# SCH_CapibaraZero_Navigation_Board_2024-0.net
KiCad netlist of a schematic drawn in EasyEDA
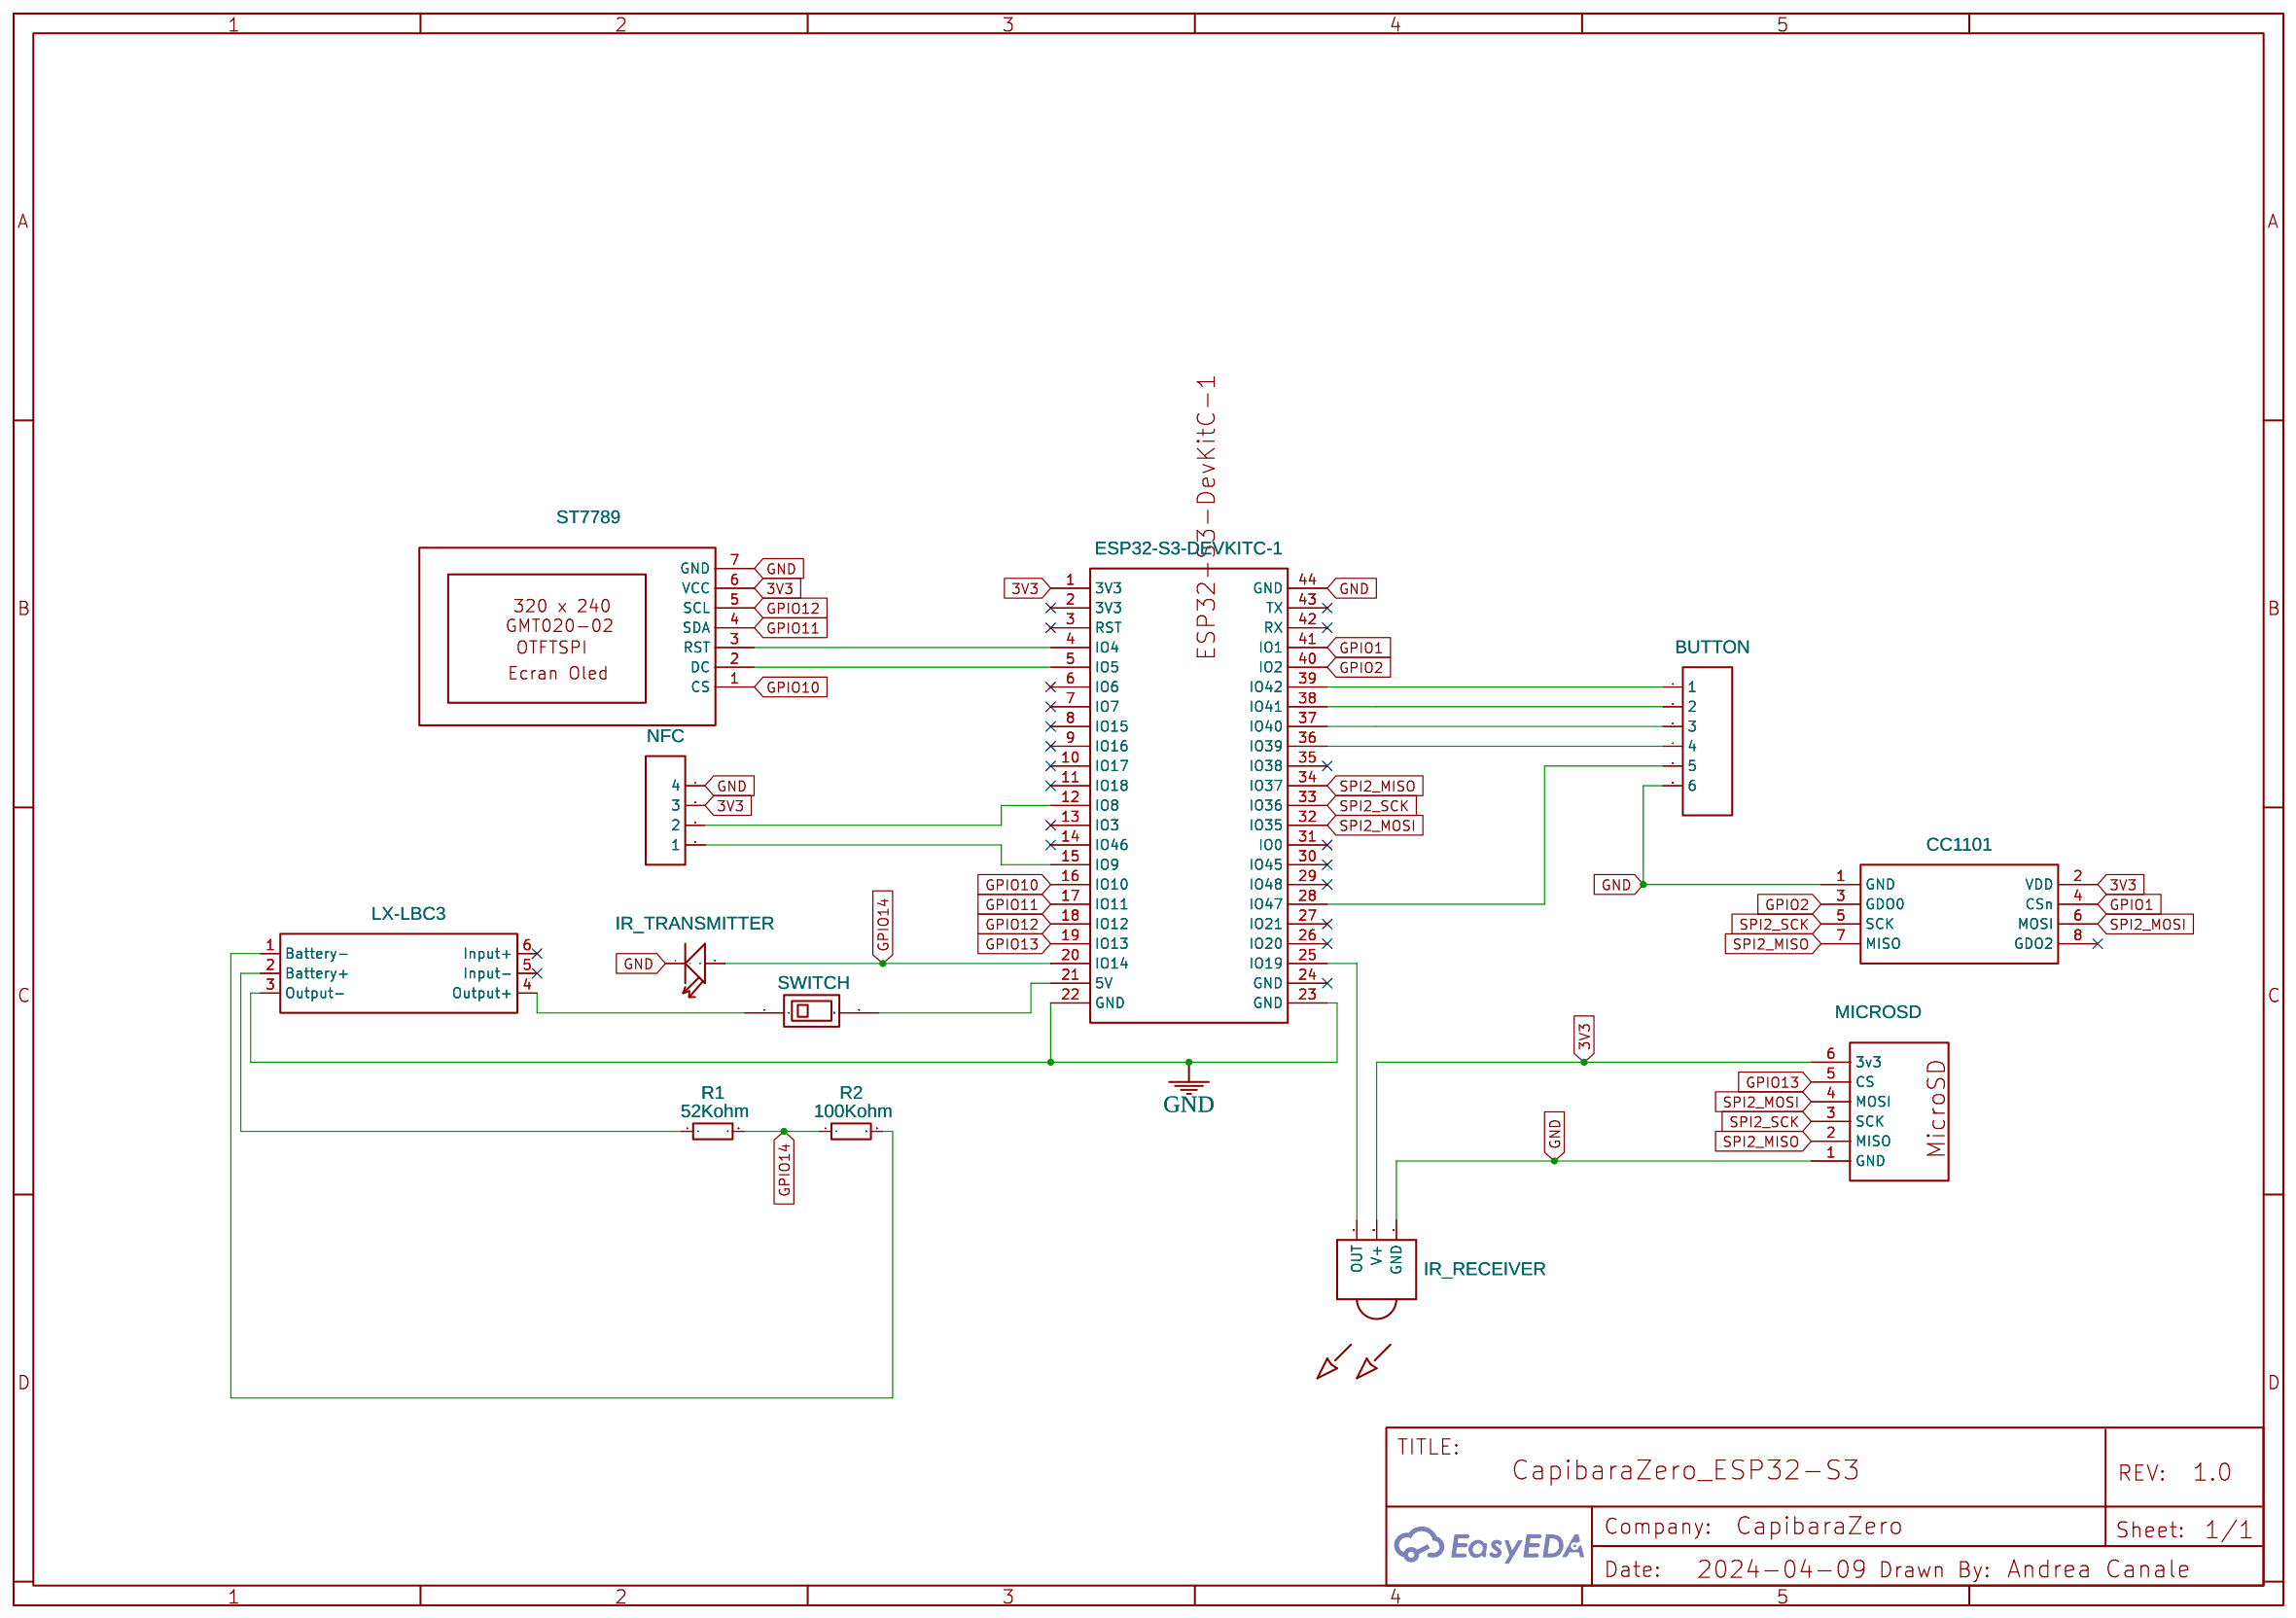
[diagram p0: CapibaraZero_Main_Scheme]
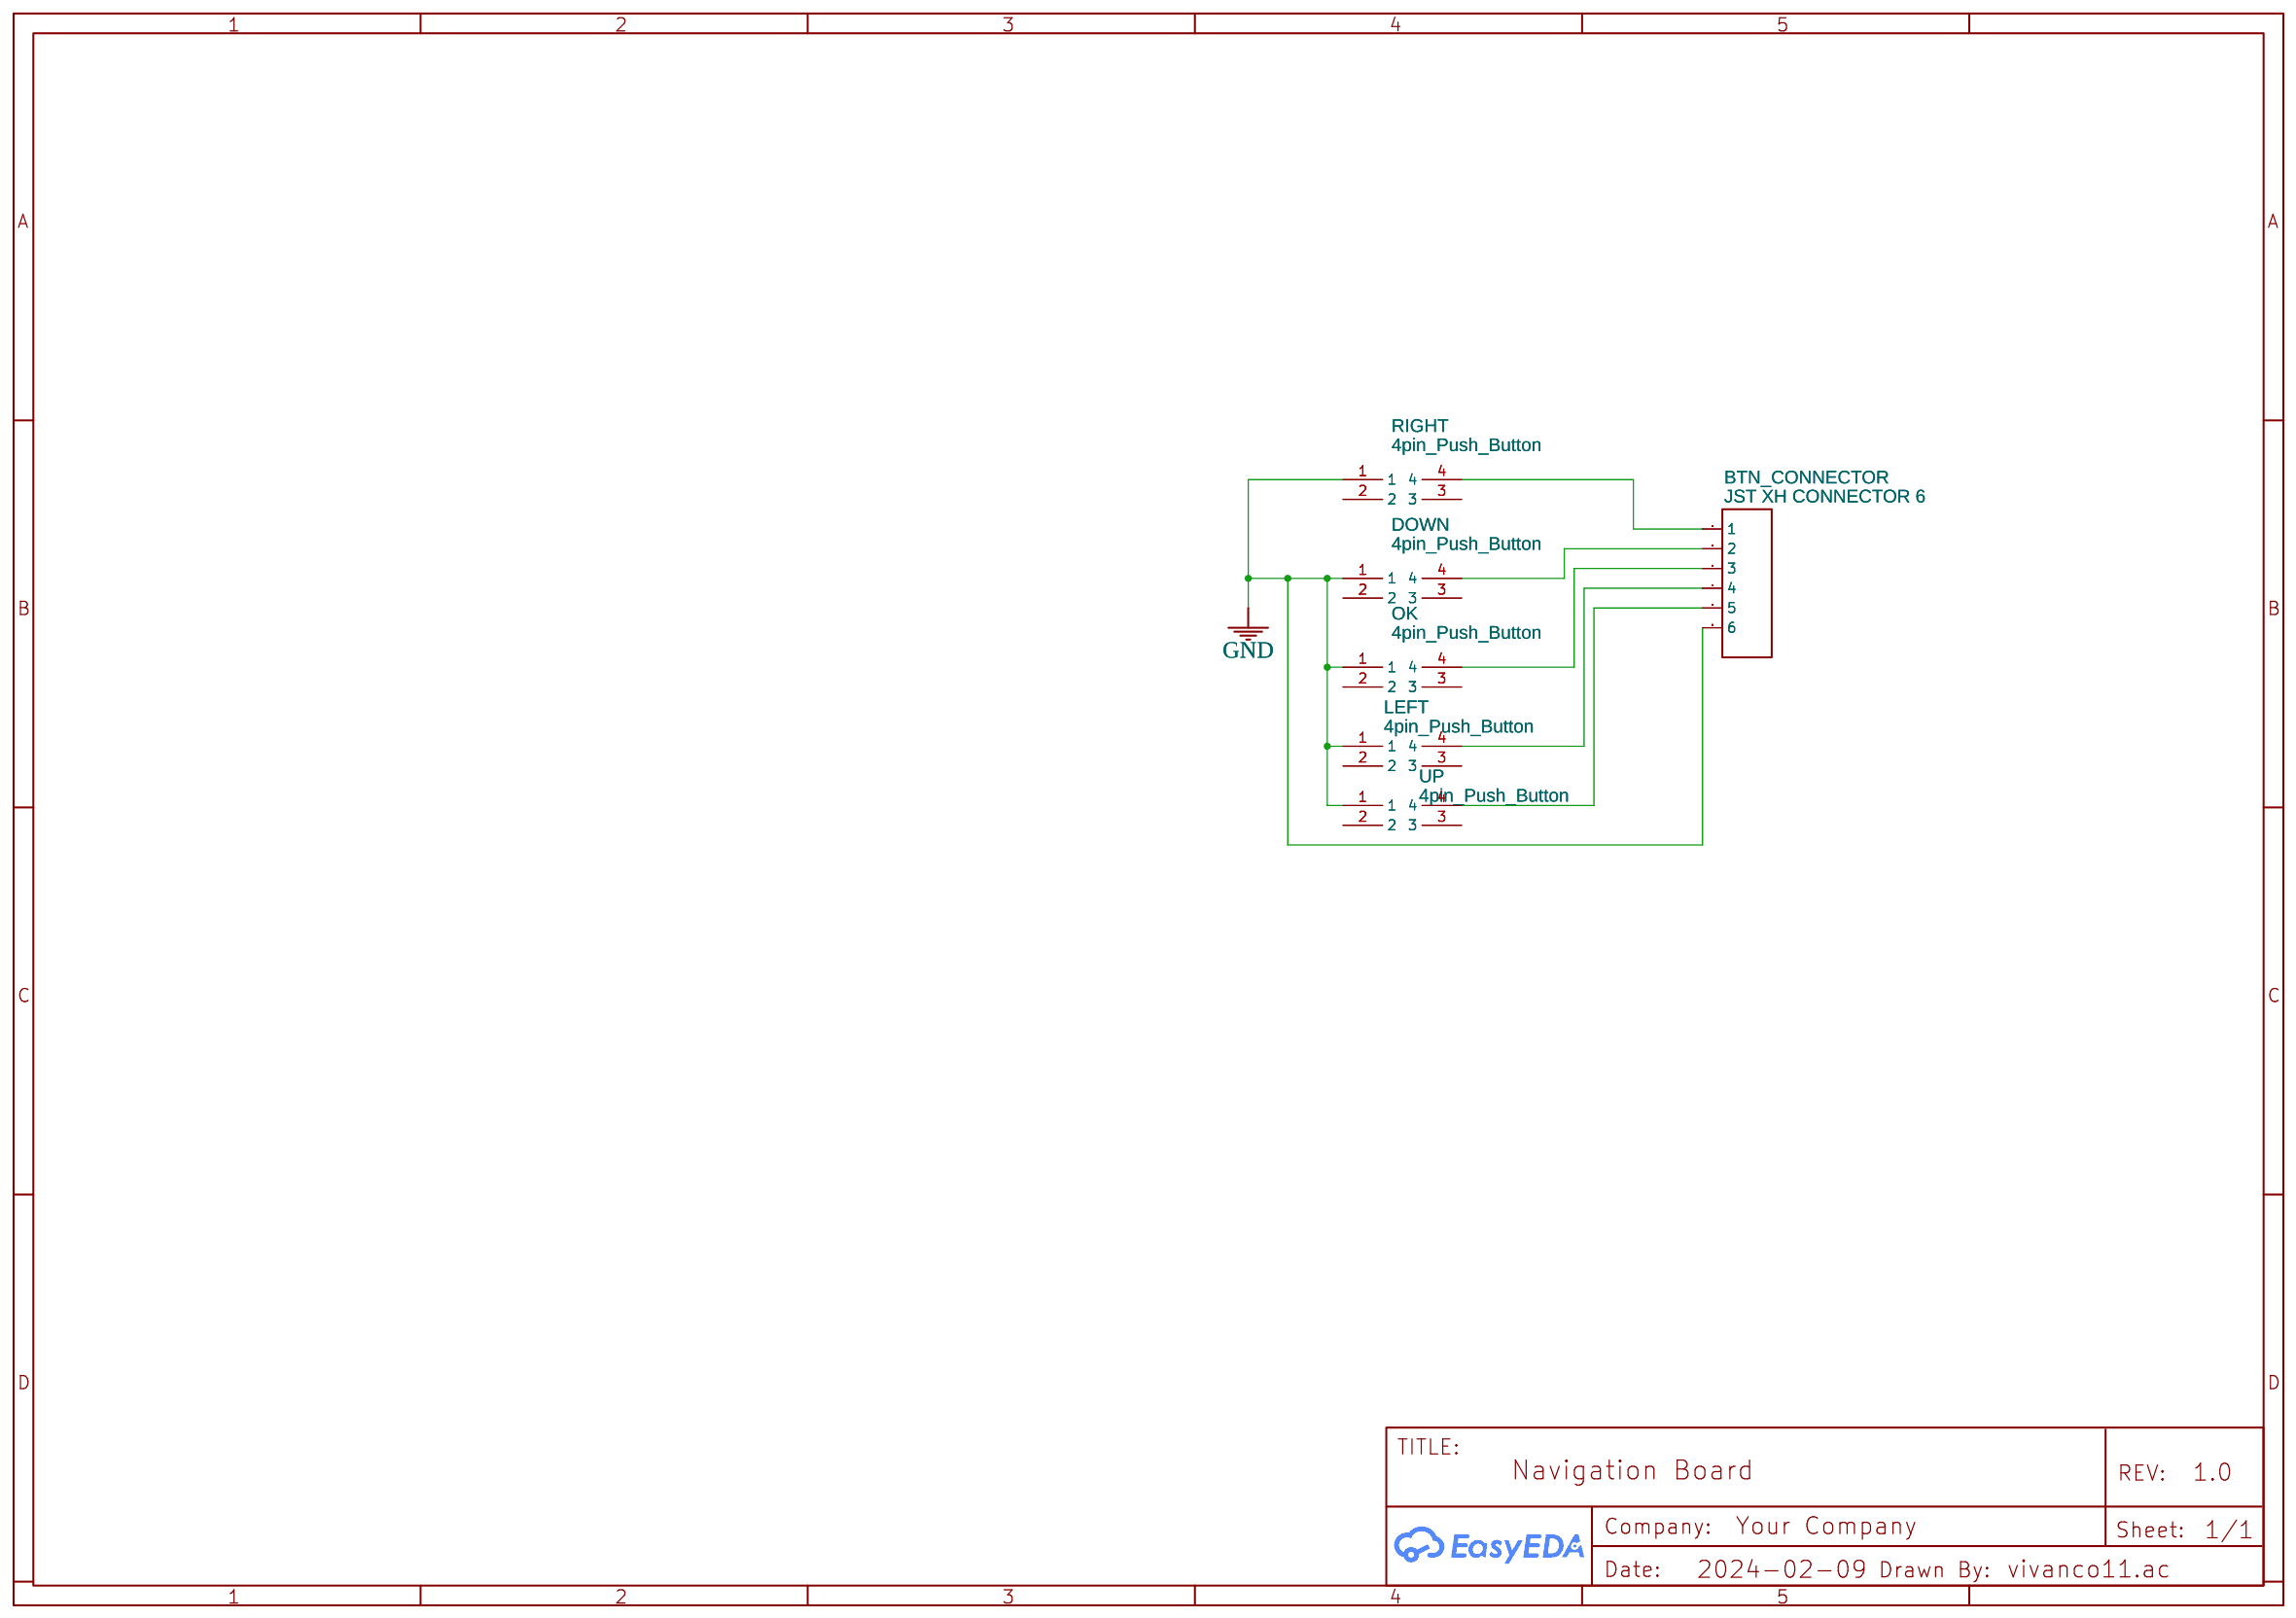
[diagram p1: Navigation board]

(export (version "E")
  (design (tool "Eeschema 10.0.6"))
  (components
    (comp (ref "BUTTON")
      (value "BTN Connector")
      (fields (field (name "Manufacturer Part") "JST_XH CONNECTOR"))
      (libsource (lib "") (part "JST XH CONNECTOR 6"))
    )
    (comp (ref "CC1101")
      (value "CC1101 E07-M1101D")
      (fields
        (field (name "Manufacturer Part") "E07-M1101D-SMA")
        (field (name "Manufacturer") "Chengdu Ebyte Electronic Technology Co., Ltd.")
      )
      (libsource (lib "") (part "CC1101 E07-M1101D"))
    )
    (comp (ref "ESP32-S3-DEVKITC-1")
      (value "ESP32-S3-DevKitC-1 development board")
      (fields (field (name "Manufacturer") "Espressif"))
      (libsource (lib "") (part "ESP32-S3-DevKitC-1 development board"))
    )
    (comp (ref "IR_RECEIVER") (value "IR RECEIVER") (libsource (lib "") (part "IR TRANSMITTER")))
    (comp (ref "IR_TRANSMITTER")
      (value "DIP-IR-LED-940NM(2P-D5MM)")
      (fields (field (name "Manufacturer Part") "IR523B-W60W1"))
      (libsource (lib "") (part "DIP-IR-LED-940NM(2P-D5MM)"))
    )
    (comp (ref "LX-LBC3") (value "LX-LBC3") (libsource (lib "") (part "LX-LBC3")))
    (comp (ref "MICROSD") (value "MicroSDSPI") (libsource (lib "") (part "MicroSDSPI")))
    (comp (ref "NFC")
      (value "NFC Connector")
      (fields (field (name "Manufacturer Part") "JST_XH CONNECTOR"))
      (libsource (lib "") (part "JST XH CONNECTOR 4"))
    )
    (comp (ref "R1")
      (value "52Kohm")
      (fields
        (field (name "Manufacturer Part") "EWWR0001J20R0T9")
        (field (name "Manufacturer") "ResistorToday")
      )
      (libsource (lib "") (part "Resistor Normal"))
    )
    (comp (ref "R2")
      (value "100Kohm")
      (fields
        (field (name "Manufacturer Part") "EWWR0001J20R0T9")
        (field (name "Manufacturer") "ResistorToday")
      )
      (libsource (lib "") (part "Resistor Normal"))
    )
    (comp (ref "ST7789")
      (value "ST7789_Display_320x240_SPI")
      (libsource (lib "") (part "ST7789_Display_320x240_SPI"))
    )
    (comp (ref "SWITCH") (value "1 Pole DIP switch") (libsource (lib "") (part "1 Pole DIP switch")))
    (comp (ref "BTN_CONNECTOR")
      (value "JST XH CONNECTOR 6")
      (fields (field (name "Manufacturer Part") "JST_XH CONNECTOR"))
      (libsource (lib "") (part "JST XH CONNECTOR 6"))
    )
    (comp (ref "DOWN") (value "4pin_Push_Button") (libsource (lib "") (part "4pin_Push_Button_4")))
    (comp (ref "LEFT") (value "4pin_Push_Button") (libsource (lib "") (part "4pin_Push_Button_2")))
    (comp (ref "OK") (value "4pin_Push_Button") (libsource (lib "") (part "4pin_Push_Button_3")))
    (comp (ref "RIGHT") (value "4pin_Push_Button") (libsource (lib "") (part "4pin_Push_Button")))
    (comp (ref "UP") (value "4pin_Push_Button") (libsource (lib "") (part "4pin_Push_Button_1")))
  )
  (nets
    (net (code "1") (name "3V3") (class "Default")
      (node (ref "CC1101") (pin "2") (pinfunction "VDD_2") (pintype "unspecified"))
      (node (ref "ESP32-S3-DEVKITC-1") (pin "1") (pinfunction "3V3_1") (pintype "unspecified"))
      (node (ref "IR_RECEIVER") (pin "VCC") (pinfunction "V+_VCC") (pintype "unspecified"))
      (node (ref "MICROSD") (pin "6") (pinfunction "3v3_6") (pintype "unspecified"))
      (node (ref "NFC") (pin "3") (pinfunction "3_3") (pintype "unspecified"))
      (node (ref "ST7789") (pin "6") (pinfunction "VCC_6") (pintype "unspecified"))
    )
    (net (code "2") (name "GND") (class "Default")
      (node (ref "BTN_CONNECTOR") (pin "6") (pinfunction "6_6") (pintype "unspecified"))
      (node (ref "BUTTON") (pin "6") (pinfunction "6_6") (pintype "unspecified"))
      (node (ref "CC1101") (pin "1") (pinfunction "GND_1") (pintype "unspecified"))
      (node (ref "DOWN") (pin "1") (pinfunction "1_1") (pintype "unspecified"))
      (node (ref "ESP32-S3-DEVKITC-1") (pin "22") (pinfunction "GND_22") (pintype "unspecified"))
      (node (ref "ESP32-S3-DEVKITC-1") (pin "23") (pinfunction "GND_23") (pintype "unspecified"))
      (node (ref "ESP32-S3-DEVKITC-1") (pin "44") (pinfunction "GND_44") (pintype "unspecified"))
      (node (ref "IR_RECEIVER") (pin "GND") (pinfunction "GND_GND") (pintype "unspecified"))
      (node (ref "IR_TRANSMITTER") (pin "-") (pinfunction "-_-") (pintype "unspecified"))
      (node (ref "LEFT") (pin "1") (pinfunction "1_1") (pintype "unspecified"))
      (node (ref "LX-LBC3") (pin "3") (pinfunction "Output-_3") (pintype "unspecified"))
      (node (ref "MICROSD") (pin "1") (pinfunction "GND_1") (pintype "unspecified"))
      (node (ref "NFC") (pin "4") (pinfunction "4_4") (pintype "unspecified"))
      (node (ref "OK") (pin "1") (pinfunction "1_1") (pintype "unspecified"))
      (node (ref "RIGHT") (pin "1") (pinfunction "1_1") (pintype "unspecified"))
      (node (ref "ST7789") (pin "7") (pinfunction "GND_7") (pintype "unspecified"))
      (node (ref "UP") (pin "1") (pinfunction "1_1") (pintype "unspecified"))
    )
    (net (code "3") (name "GPIO1") (class "Default")
      (node (ref "CC1101") (pin "4") (pinfunction "CSn_4") (pintype "unspecified"))
      (node (ref "ESP32-S3-DEVKITC-1") (pin "41") (pinfunction "IO1_41") (pintype "unspecified"))
    )
    (net (code "4") (name "GPIO2") (class "Default")
      (node (ref "CC1101") (pin "3") (pinfunction "GDO0_3") (pintype "unspecified"))
      (node (ref "ESP32-S3-DEVKITC-1") (pin "40") (pinfunction "IO2_40") (pintype "unspecified"))
    )
    (net (code "5") (name "GPIO10") (class "Default")
      (node (ref "ESP32-S3-DEVKITC-1") (pin "16") (pinfunction "IO10_16") (pintype "unspecified"))
      (node (ref "ST7789") (pin "1") (pinfunction "CS_1") (pintype "unspecified"))
    )
    (net (code "6") (name "GPIO11") (class "Default")
      (node (ref "ESP32-S3-DEVKITC-1") (pin "17") (pinfunction "IO11_17") (pintype "unspecified"))
      (node (ref "ST7789") (pin "4") (pinfunction "SDA_4") (pintype "unspecified"))
    )
    (net (code "7") (name "GPIO12") (class "Default")
      (node (ref "ESP32-S3-DEVKITC-1") (pin "18") (pinfunction "IO12_18") (pintype "unspecified"))
      (node (ref "ST7789") (pin "5") (pinfunction "SCL_5") (pintype "unspecified"))
    )
    (net (code "8") (name "GPIO13") (class "Default")
      (node (ref "ESP32-S3-DEVKITC-1") (pin "19") (pinfunction "IO13_19") (pintype "unspecified"))
      (node (ref "MICROSD") (pin "5") (pinfunction "CS_5") (pintype "unspecified"))
    )
    (net (code "9") (name "GPIO14") (class "Default")
      (node (ref "ESP32-S3-DEVKITC-1") (pin "20") (pinfunction "IO14_20") (pintype "unspecified"))
      (node (ref "IR_TRANSMITTER") (pin "+") (pinfunction "+_+") (pintype "unspecified"))
      (node (ref "R1") (pin "2") (pinfunction "2_2") (pintype "unspecified"))
      (node (ref "R2") (pin "1") (pinfunction "1_1") (pintype "unspecified"))
    )
    (net (code "10") (name "Net-(BTN_CONNECTOR-Pad1)") (class "Default")
      (node (ref "BTN_CONNECTOR") (pin "1") (pinfunction "1_1") (pintype "unspecified"))
      (node (ref "RIGHT") (pin "4") (pinfunction "4_4") (pintype "unspecified"))
    )
    (net (code "11") (name "Net-(BTN_CONNECTOR-Pad2)") (class "Default")
      (node (ref "BTN_CONNECTOR") (pin "2") (pinfunction "2_2") (pintype "unspecified"))
      (node (ref "DOWN") (pin "4") (pinfunction "4_4") (pintype "unspecified"))
    )
    (net (code "12") (name "Net-(BTN_CONNECTOR-Pad3)") (class "Default")
      (node (ref "BTN_CONNECTOR") (pin "3") (pinfunction "3_3") (pintype "unspecified"))
      (node (ref "OK") (pin "4") (pinfunction "4_4") (pintype "unspecified"))
    )
    (net (code "13") (name "Net-(BTN_CONNECTOR-Pad4)") (class "Default")
      (node (ref "BTN_CONNECTOR") (pin "4") (pinfunction "4_4") (pintype "unspecified"))
      (node (ref "LEFT") (pin "4") (pinfunction "4_4") (pintype "unspecified"))
    )
    (net (code "14") (name "Net-(BTN_CONNECTOR-Pad5)") (class "Default")
      (node (ref "BTN_CONNECTOR") (pin "5") (pinfunction "5_5") (pintype "unspecified"))
      (node (ref "UP") (pin "4") (pinfunction "4_4") (pintype "unspecified"))
    )
    (net (code "15") (name "Net-(ESP32-S3-DEVKITC-1-5V)") (class "Default")
      (node (ref "ESP32-S3-DEVKITC-1") (pin "21") (pinfunction "5V_21") (pintype "unspecified"))
      (node (ref "SWITCH") (pin "2") (pinfunction "OUT_2") (pintype "unspecified"))
    )
    (net (code "16") (name "Net-(ESP32-S3-DEVKITC-1-IO4)") (class "Default")
      (node (ref "ESP32-S3-DEVKITC-1") (pin "4") (pinfunction "IO4_4") (pintype "unspecified"))
      (node (ref "ST7789") (pin "3") (pinfunction "RST_3") (pintype "unspecified"))
    )
    (net (code "17") (name "Net-(ESP32-S3-DEVKITC-1-IO5)") (class "Default")
      (node (ref "ESP32-S3-DEVKITC-1") (pin "5") (pinfunction "IO5_5") (pintype "unspecified"))
      (node (ref "ST7789") (pin "2") (pinfunction "DC_2") (pintype "unspecified"))
    )
    (net (code "18") (name "Net-(ESP32-S3-DEVKITC-1-IO8)") (class "Default")
      (node (ref "ESP32-S3-DEVKITC-1") (pin "12") (pinfunction "IO8_12") (pintype "unspecified"))
      (node (ref "NFC") (pin "2") (pinfunction "2_2") (pintype "unspecified"))
    )
    (net (code "19") (name "Net-(ESP32-S3-DEVKITC-1-IO9)") (class "Default")
      (node (ref "ESP32-S3-DEVKITC-1") (pin "15") (pinfunction "IO9_15") (pintype "unspecified"))
      (node (ref "NFC") (pin "1") (pinfunction "1_1") (pintype "unspecified"))
    )
    (net (code "20") (name "Net-(ESP32-S3-DEVKITC-1-IO19)") (class "Default")
      (node (ref "ESP32-S3-DEVKITC-1") (pin "25") (pinfunction "IO19_25") (pintype "unspecified"))
      (node (ref "IR_RECEIVER") (pin "OUT") (pinfunction "OUT_OUT") (pintype "unspecified"))
    )
    (net (code "21") (name "Net-(ESP32-S3-DEVKITC-1-IO39)") (class "Default")
      (node (ref "BUTTON") (pin "4") (pinfunction "4_4") (pintype "unspecified"))
      (node (ref "ESP32-S3-DEVKITC-1") (pin "36") (pinfunction "IO39_36") (pintype "unspecified"))
    )
    (net (code "22") (name "Net-(ESP32-S3-DEVKITC-1-IO40)") (class "Default")
      (node (ref "BUTTON") (pin "3") (pinfunction "3_3") (pintype "unspecified"))
      (node (ref "ESP32-S3-DEVKITC-1") (pin "37") (pinfunction "IO40_37") (pintype "unspecified"))
    )
    (net (code "23") (name "Net-(ESP32-S3-DEVKITC-1-IO41)") (class "Default")
      (node (ref "BUTTON") (pin "2") (pinfunction "2_2") (pintype "unspecified"))
      (node (ref "ESP32-S3-DEVKITC-1") (pin "38") (pinfunction "IO41_38") (pintype "unspecified"))
    )
    (net (code "24") (name "Net-(ESP32-S3-DEVKITC-1-IO42)") (class "Default")
      (node (ref "BUTTON") (pin "1") (pinfunction "1_1") (pintype "unspecified"))
      (node (ref "ESP32-S3-DEVKITC-1") (pin "39") (pinfunction "IO42_39") (pintype "unspecified"))
    )
    (net (code "25") (name "Net-(ESP32-S3-DEVKITC-1-IO47)") (class "Default")
      (node (ref "BUTTON") (pin "5") (pinfunction "5_5") (pintype "unspecified"))
      (node (ref "ESP32-S3-DEVKITC-1") (pin "28") (pinfunction "IO47_28") (pintype "unspecified"))
    )
    (net (code "26") (name "Net-(LX-LBC3-Battery+)") (class "Default")
      (node (ref "LX-LBC3") (pin "2") (pinfunction "Battery+_2") (pintype "unspecified"))
      (node (ref "R1") (pin "1") (pinfunction "1_1") (pintype "unspecified"))
    )
    (net (code "27") (name "Net-(LX-LBC3-Battery-)") (class "Default")
      (node (ref "LX-LBC3") (pin "1") (pinfunction "Battery-_1") (pintype "unspecified"))
      (node (ref "R2") (pin "2") (pinfunction "2_2") (pintype "unspecified"))
    )
    (net (code "28") (name "Net-(LX-LBC3-Output+)") (class "Default")
      (node (ref "LX-LBC3") (pin "4") (pinfunction "Output+_4") (pintype "unspecified"))
      (node (ref "SWITCH") (pin "1") (pinfunction "IN_1") (pintype "unspecified"))
    )
    (net (code "29") (name "SPI2_MISO") (class "Default")
      (node (ref "CC1101") (pin "7") (pinfunction "MISO_7") (pintype "unspecified"))
      (node (ref "ESP32-S3-DEVKITC-1") (pin "34") (pinfunction "IO37_34") (pintype "unspecified"))
      (node (ref "MICROSD") (pin "2") (pinfunction "MISO_2") (pintype "unspecified"))
    )
    (net (code "30") (name "SPI2_MOSI") (class "Default")
      (node (ref "CC1101") (pin "6") (pinfunction "MOSI_6") (pintype "unspecified"))
      (node (ref "ESP32-S3-DEVKITC-1") (pin "32") (pinfunction "IO35_32") (pintype "unspecified"))
      (node (ref "MICROSD") (pin "4") (pinfunction "MOSI_4") (pintype "unspecified"))
    )
    (net (code "31") (name "SPI2_SCK") (class "Default")
      (node (ref "CC1101") (pin "5") (pinfunction "SCK_5") (pintype "unspecified"))
      (node (ref "ESP32-S3-DEVKITC-1") (pin "33") (pinfunction "IO36_33") (pintype "unspecified"))
      (node (ref "MICROSD") (pin "3") (pinfunction "SCK_3") (pintype "unspecified"))
    )
    (net (code "32") (name "unconnected-(CC1101-GDO2-Pad8)") (class "Default")
      (node (ref "CC1101") (pin "8") (pinfunction "GDO2_8") (pintype "unspecified+no_connect"))
    )
    (net (code "33") (name "unconnected-(DOWN-Pad2)") (class "Default")
      (node (ref "DOWN") (pin "2") (pinfunction "2_2") (pintype "unspecified"))
    )
    (net (code "34") (name "unconnected-(DOWN-Pad3)") (class "Default")
      (node (ref "DOWN") (pin "3") (pinfunction "3_3") (pintype "unspecified"))
    )
    (net (code "35") (name "unconnected-(ESP32-S3-DEVKITC-1-3V3-Pad2)") (class "Default")
      (node (ref "ESP32-S3-DEVKITC-1") (pin "2") (pinfunction "3V3_2") (pintype "unspecified+no_connect"))
    )
    (net (code "36") (name "unconnected-(ESP32-S3-DEVKITC-1-GND-Pad24)") (class "Default")
      (node (ref "ESP32-S3-DEVKITC-1") (pin "24") (pinfunction "GND_24") (pintype "unspecified+no_connect"))
    )
    (net (code "37") (name "unconnected-(ESP32-S3-DEVKITC-1-IO0-Pad31)") (class "Default")
      (node (ref "ESP32-S3-DEVKITC-1") (pin "31") (pinfunction "IO0_31") (pintype "unspecified+no_connect"))
    )
    (net (code "38") (name "unconnected-(ESP32-S3-DEVKITC-1-IO3-Pad13)") (class "Default")
      (node (ref "ESP32-S3-DEVKITC-1") (pin "13") (pinfunction "IO3_13") (pintype "unspecified+no_connect"))
    )
    (net (code "39") (name "unconnected-(ESP32-S3-DEVKITC-1-IO6-Pad6)") (class "Default")
      (node (ref "ESP32-S3-DEVKITC-1") (pin "6") (pinfunction "IO6_6") (pintype "unspecified+no_connect"))
    )
    (net (code "40") (name "unconnected-(ESP32-S3-DEVKITC-1-IO7-Pad7)") (class "Default")
      (node (ref "ESP32-S3-DEVKITC-1") (pin "7") (pinfunction "IO7_7") (pintype "unspecified+no_connect"))
    )
    (net (code "41") (name "unconnected-(ESP32-S3-DEVKITC-1-IO15-Pad8)") (class "Default")
      (node (ref "ESP32-S3-DEVKITC-1") (pin "8") (pinfunction "IO15_8") (pintype "unspecified+no_connect"))
    )
    (net (code "42") (name "unconnected-(ESP32-S3-DEVKITC-1-IO16-Pad9)") (class "Default")
      (node (ref "ESP32-S3-DEVKITC-1") (pin "9") (pinfunction "IO16_9") (pintype "unspecified+no_connect"))
    )
    (net (code "43") (name "unconnected-(ESP32-S3-DEVKITC-1-IO17-Pad10)") (class "Default")
      (node (ref "ESP32-S3-DEVKITC-1") (pin "10") (pinfunction "IO17_10") (pintype "unspecified+no_connect"))
    )
    (net (code "44") (name "unconnected-(ESP32-S3-DEVKITC-1-IO18-Pad11)") (class "Default")
      (node (ref "ESP32-S3-DEVKITC-1") (pin "11") (pinfunction "IO18_11") (pintype "unspecified+no_connect"))
    )
    (net (code "45") (name "unconnected-(ESP32-S3-DEVKITC-1-IO20-Pad26)") (class "Default")
      (node (ref "ESP32-S3-DEVKITC-1") (pin "26") (pinfunction "IO20_26") (pintype "unspecified+no_connect"))
    )
    (net (code "46") (name "unconnected-(ESP32-S3-DEVKITC-1-IO21-Pad27)") (class "Default")
      (node (ref "ESP32-S3-DEVKITC-1") (pin "27") (pinfunction "IO21_27") (pintype "unspecified+no_connect"))
    )
    (net (code "47") (name "unconnected-(ESP32-S3-DEVKITC-1-IO38-Pad35)") (class "Default")
      (node (ref "ESP32-S3-DEVKITC-1") (pin "35") (pinfunction "IO38_35") (pintype "unspecified+no_connect"))
    )
    (net (code "48") (name "unconnected-(ESP32-S3-DEVKITC-1-IO45-Pad30)") (class "Default")
      (node (ref "ESP32-S3-DEVKITC-1") (pin "30") (pinfunction "IO45_30") (pintype "unspecified+no_connect"))
    )
    (net (code "49") (name "unconnected-(ESP32-S3-DEVKITC-1-IO46-Pad14)") (class "Default")
      (node (ref "ESP32-S3-DEVKITC-1") (pin "14") (pinfunction "IO46_14") (pintype "unspecified+no_connect"))
    )
    (net (code "50") (name "unconnected-(ESP32-S3-DEVKITC-1-IO48-Pad29)") (class "Default")
      (node (ref "ESP32-S3-DEVKITC-1") (pin "29") (pinfunction "IO48_29") (pintype "unspecified+no_connect"))
    )
    (net (code "51") (name "unconnected-(ESP32-S3-DEVKITC-1-RST-Pad3)") (class "Default")
      (node (ref "ESP32-S3-DEVKITC-1") (pin "3") (pinfunction "RST_3") (pintype "unspecified+no_connect"))
    )
    (net (code "52") (name "unconnected-(ESP32-S3-DEVKITC-1-RX-Pad42)") (class "Default")
      (node (ref "ESP32-S3-DEVKITC-1") (pin "42") (pinfunction "RX_42") (pintype "unspecified+no_connect"))
    )
    (net (code "53") (name "unconnected-(ESP32-S3-DEVKITC-1-TX-Pad43)") (class "Default")
      (node (ref "ESP32-S3-DEVKITC-1") (pin "43") (pinfunction "TX_43") (pintype "unspecified+no_connect"))
    )
    (net (code "54") (name "unconnected-(LEFT-Pad2)") (class "Default")
      (node (ref "LEFT") (pin "2") (pinfunction "2_2") (pintype "unspecified"))
    )
    (net (code "55") (name "unconnected-(LEFT-Pad3)") (class "Default")
      (node (ref "LEFT") (pin "3") (pinfunction "3_3") (pintype "unspecified"))
    )
    (net (code "56") (name "unconnected-(LX-LBC3-Input+-Pad6)") (class "Default")
      (node (ref "LX-LBC3") (pin "6") (pinfunction "Input+_6") (pintype "unspecified+no_connect"))
    )
    (net (code "57") (name "unconnected-(LX-LBC3-Input--Pad5)") (class "Default")
      (node (ref "LX-LBC3") (pin "5") (pinfunction "Input-_5") (pintype "unspecified+no_connect"))
    )
    (net (code "58") (name "unconnected-(OK-Pad2)") (class "Default")
      (node (ref "OK") (pin "2") (pinfunction "2_2") (pintype "unspecified"))
    )
    (net (code "59") (name "unconnected-(OK-Pad3)") (class "Default")
      (node (ref "OK") (pin "3") (pinfunction "3_3") (pintype "unspecified"))
    )
    (net (code "60") (name "unconnected-(RIGHT-Pad2)") (class "Default")
      (node (ref "RIGHT") (pin "2") (pinfunction "2_2") (pintype "unspecified"))
    )
    (net (code "61") (name "unconnected-(RIGHT-Pad3)") (class "Default")
      (node (ref "RIGHT") (pin "3") (pinfunction "3_3") (pintype "unspecified"))
    )
    (net (code "62") (name "unconnected-(UP-Pad2)") (class "Default")
      (node (ref "UP") (pin "2") (pinfunction "2_2") (pintype "unspecified"))
    )
    (net (code "63") (name "unconnected-(UP-Pad3)") (class "Default")
      (node (ref "UP") (pin "3") (pinfunction "3_3") (pintype "unspecified"))
    )
  )
)
